# Relay3_Block.net
KiCad netlist of a schematic drawn in Altium Designer
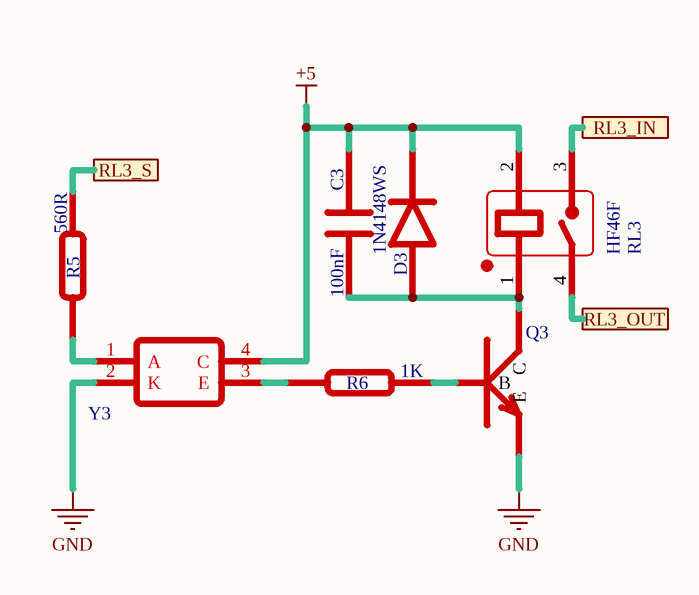
[diagram p0: Relay3_Block.SchDoc]

(export (version "E")
  (design (tool "Eeschema 10.0.6"))
  (components
    (comp (ref "C3")
      (value "100nF")
      (footprint "C0805")
      (description "Ceramic Capacitor")
      (libsource (lib "CTAI-Library") (part "CAP-CER"))
    )
    (comp (ref "D3")
      (value "1N4148WS")
      (footprint "SMA")
      (description "Small Signal Diode")
      (libsource (lib "CTAI-Library") (part "1N4148WS"))
    )
    (comp (ref "Q3")
      (value "S8050")
      (footprint "SOT-23")
      (description "NPN Transistors 0.5A Collector to Emitter 25V")
      (libsource (lib "CTAI-Library") (part "S8050"))
    )
    (comp (ref "R5")
      (value "560R")
      (footprint "R0603")
      (description "Resistor")
      (libsource (lib "CTAI-Library") (part "Resistor"))
    )
    (comp (ref "R6")
      (value "1K")
      (footprint "R0603")
      (description "Resistor")
      (libsource (lib "CTAI-Library") (part "Resistor"))
    )
    (comp (ref "RL3")
      (value "HF46F")
      (footprint "HF-46-X")
      (description "Relay 4 Pin")
      (libsource (lib "CTAI-Library") (part "HF46F"))
    )
    (comp (ref "Y3")
      (value "PHOTOCOUPLER")
      (footprint "SOP-4")
      (description "Photo-Coupler")
      (libsource (lib "CTAI-Library") (part "PC817"))
    )
  )
  (nets
    (net (code "1") (name "+5") (class "Default")
      (node (ref "C3") (pin "2") (pintype "passive"))
      (node (ref "D3") (pin "K") (pinfunction "K_K") (pintype "passive"))
      (node (ref "RL3") (pin "2") (pinfunction "2_2") (pintype "passive"))
      (node (ref "Y3") (pin "4") (pinfunction "C_4") (pintype "passive"))
    )
    (net (code "2") (name "/RL3_IN") (class "Default")
      (node (ref "RL3") (pin "3") (pinfunction "3_3") (pintype "passive"))
    )
    (net (code "3") (name "/RL3_OUT") (class "Default")
      (node (ref "RL3") (pin "4") (pinfunction "4_4") (pintype "passive"))
    )
    (net (code "4") (name "/RL3_S") (class "Default")
      (node (ref "R5") (pin "1") (pinfunction "1_1") (pintype "passive"))
    )
    (net (code "5") (name "GND") (class "Default")
      (node (ref "Q3") (pin "2") (pinfunction "E_2") (pintype "passive"))
      (node (ref "Y3") (pin "2") (pinfunction "K_2") (pintype "passive"))
    )
    (net (code "6") (name "Net-(Q3-B)") (class "Default")
      (node (ref "Q3") (pin "1") (pinfunction "B_1") (pintype "passive"))
      (node (ref "R6") (pin "1") (pinfunction "1_1") (pintype "passive"))
    )
    (net (code "7") (name "Net-(Q3-C)") (class "Default")
      (node (ref "C3") (pin "1") (pintype "passive"))
      (node (ref "D3") (pin "A") (pinfunction "A_A") (pintype "passive"))
      (node (ref "Q3") (pin "3") (pinfunction "C_3") (pintype "passive"))
      (node (ref "RL3") (pin "1") (pinfunction "1_1") (pintype "passive"))
    )
    (net (code "8") (name "Net-(Y3-A)") (class "Default")
      (node (ref "R5") (pin "2") (pinfunction "2_2") (pintype "passive"))
      (node (ref "Y3") (pin "1") (pinfunction "A_1") (pintype "passive"))
    )
    (net (code "9") (name "Net-(Y3-E)") (class "Default")
      (node (ref "R6") (pin "2") (pinfunction "2_2") (pintype "passive"))
      (node (ref "Y3") (pin "3") (pinfunction "E_3") (pintype "passive"))
    )
  )
)
